# LTE_Module.net
KiCad netlist of a schematic drawn in Altium Designer
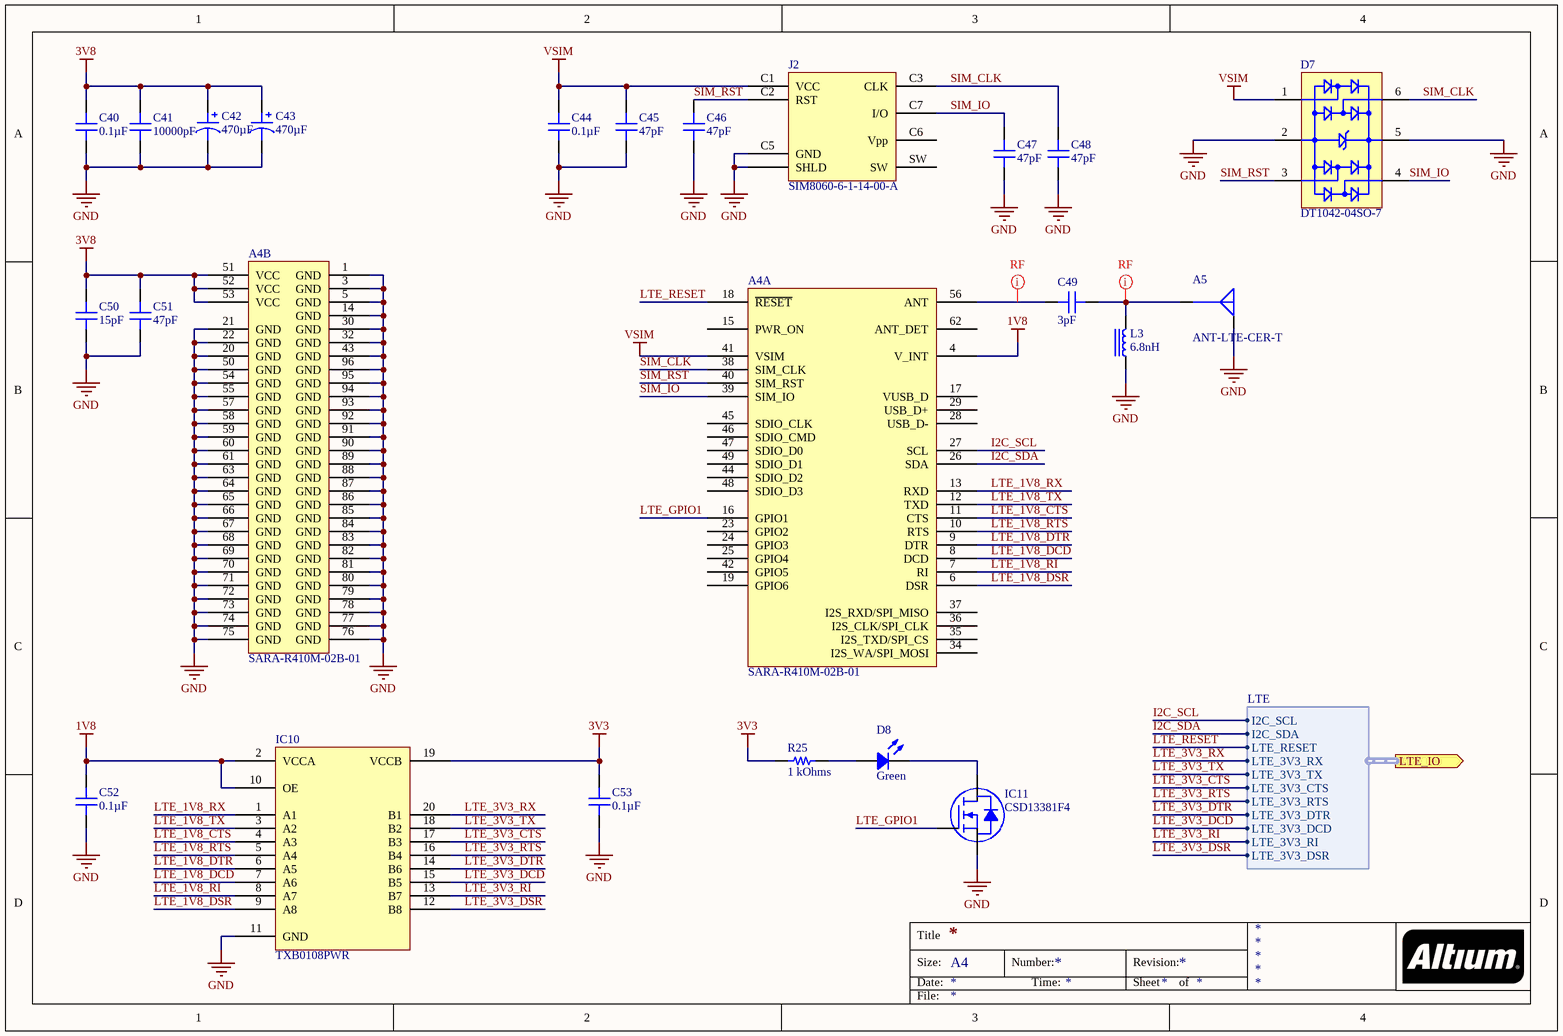
[diagram p0: LTE Module.SchDoc]

(export (version "E")
  (design (tool "Eeschema 10.0.6"))
  (components
    (comp (ref "A4")
      (value "SARA-R410M-02B-01")
      (footprint "U-BLOX SARA-R4")
      (description "RF TXRX CELL 4G LTE CATM1/NB-IOT")
      (fields (field (name "MANUFACTURER") "U-Blox America Inc."))
      (libsource (lib "Celestial Altium Library - altium_library") (part "U-BLOX SARA-R410M-02B-01"))
    )
    (comp (ref "A5")
      (value "ANT-LTE-CER-T")
      (footprint "LINX ANT-LTE-CER-T")
      (description "RF ANT 829MHZ/1.94GHZ CHIP SLD")
      (fields (field (name "MANUFACTURER") "Linx Technologies Inc."))
      (libsource (lib "Celestial Altium Library - altium_library") (part "Basic Antenna"))
    )
    (comp (ref "C40")
      (value "0.1µF")
      (footprint "CAP 0201_0603")
      (description "CAP CER 0.1UF 16V X5R 0201")
      (fields
        (field (name "PART NUMBER") "GRM033R61C104ME84D")
        (field (name "MANUFACTURER") "Murata Electronics")
      )
      (libsource (lib "Celestial Altium Library - altium_library") (part "Capacitor"))
    )
    (comp (ref "C41")
      (value "10000pF")
      (footprint "CAP 0201_0603")
      (description "CAP CER 10000PF 6.3V X7R 0201")
      (fields
        (field (name "PART NUMBER") "CGA1A2X7R0J103M030BA")
        (field (name "MANUFACTURER") "TDK Corporation")
      )
      (libsource (lib "Celestial Altium Library - altium_library") (part "Capacitor"))
    )
    (comp (ref "C42")
      (value "470µF")
      (footprint "CAP POL 1411_3528")
      (description "CAP TANT 470UF 20% 6.3V 1411")
      (fields (field (name "PART NUMBER") "F950J477MBAAQ2") (field (name "MANUFACTURER") "AVX Corporation"))
      (libsource (lib "Celestial Altium Library - altium_library") (part "Polarised Capacitor"))
    )
    (comp (ref "C43")
      (value "470µF")
      (footprint "CAP POL 1411_3528")
      (description "CAP TANT 470UF 20% 6.3V 1411")
      (fields (field (name "PART NUMBER") "F950J477MBAAQ2") (field (name "MANUFACTURER") "AVX Corporation"))
      (libsource (lib "Celestial Altium Library - altium_library") (part "Polarised Capacitor"))
    )
    (comp (ref "C44")
      (value "0.1µF")
      (footprint "CAP 0201_0603")
      (description "CAP CER 0.1UF 16V X5R 0201")
      (fields
        (field (name "PART NUMBER") "GRM033R61C104ME84D")
        (field (name "MANUFACTURER") "Murata Electronics")
      )
      (libsource (lib "Celestial Altium Library - altium_library") (part "Capacitor"))
    )
    (comp (ref "C45")
      (value "47pF")
      (footprint "CAP 0201_0603")
      (description "CAP CER 47PF 25V NP0 0201")
      (fields (field (name "PART NUMBER") "C0201C470K3GAC7867") (field (name "MANUFACTURER") "KEMET"))
      (libsource (lib "Celestial Altium Library - altium_library") (part "Capacitor"))
    )
    (comp (ref "C46")
      (value "47pF")
      (footprint "CAP 0201_0603")
      (description "CAP CER 47PF 25V NP0 0201")
      (fields (field (name "PART NUMBER") "C0201C470K3GAC7867") (field (name "MANUFACTURER") "KEMET"))
      (libsource (lib "Celestial Altium Library - altium_library") (part "Capacitor"))
    )
    (comp (ref "C47")
      (value "47pF")
      (footprint "CAP 0201_0603")
      (description "CAP CER 47PF 25V NP0 0201")
      (fields (field (name "PART NUMBER") "C0201C470K3GAC7867") (field (name "MANUFACTURER") "KEMET"))
      (libsource (lib "Celestial Altium Library - altium_library") (part "Capacitor"))
    )
    (comp (ref "C48")
      (value "47pF")
      (footprint "CAP 0201_0603")
      (description "CAP CER 47PF 25V NP0 0201")
      (fields (field (name "PART NUMBER") "C0201C470K3GAC7867") (field (name "MANUFACTURER") "KEMET"))
      (libsource (lib "Celestial Altium Library - altium_library") (part "Capacitor"))
    )
    (comp (ref "C49")
      (value "3pF")
      (footprint "CAP 0201_0603 RF")
      (description "CAP CER 3PF 25V C0G/NP0 0201")
      (fields
        (field (name "PART NUMBER") "GJM0335C1E3R0CB01D")
        (field (name "MANUFACTURER") "Murata Electronics")
      )
      (libsource (lib "Celestial Altium Library - altium_library") (part "Capacitor"))
    )
    (comp (ref "C50")
      (value "15pF")
      (footprint "CAP 0201_0603")
      (description "CAP CER 15PF 25V C0G 0201")
      (fields
        (field (name "PART NUMBER") "CGA1A2C0G1E150J030BA")
        (field (name "MANUFACTURER") "TDK Corporation")
      )
      (libsource (lib "Celestial Altium Library - altium_library") (part "Capacitor"))
    )
    (comp (ref "C51")
      (value "47pF")
      (footprint "CAP 0201_0603")
      (description "CAP CER 47PF 25V NP0 0201")
      (fields (field (name "PART NUMBER") "C0201C470K3GAC7867") (field (name "MANUFACTURER") "KEMET"))
      (libsource (lib "Celestial Altium Library - altium_library") (part "Capacitor"))
    )
    (comp (ref "C52")
      (value "0.1µF")
      (footprint "CAP 0201_0603")
      (description "CAP CER 0.1UF 16V X5R 0201")
      (fields
        (field (name "PART NUMBER") "GRM033R61C104ME84D")
        (field (name "MANUFACTURER") "Murata Electronics")
      )
      (libsource (lib "Celestial Altium Library - altium_library") (part "Capacitor"))
    )
    (comp (ref "C53")
      (value "0.1µF")
      (footprint "CAP 0201_0603")
      (description "CAP CER 0.1UF 16V X5R 0201")
      (fields
        (field (name "PART NUMBER") "GRM033R61C104ME84D")
        (field (name "MANUFACTURER") "Murata Electronics")
      )
      (libsource (lib "Celestial Altium Library - altium_library") (part "Capacitor"))
    )
    (comp (ref "D7")
      (value "DT1042-04SO-7")
      (footprint "DIODES SOT-23-6 W6")
      (description "TVS DIODE 5V 9V SOT26")
      (fields (field (name "MANUFACTURER") "Diodes Incorporated"))
      (libsource (lib "Celestial Altium Library - altium_library") (part "DIODES SOT-23-6"))
    )
    (comp (ref "D8")
      (value "Green")
      (footprint "LED 0402_1005 GREEN")
      (description "LED GREEN CLEAR 0402 SMD")
      (fields (field (name "PART NUMBER") "QBLP595-IG") (field (name "MANUFACTURER") "QT Brightek (QTB)"))
      (libsource (lib "Celestial Altium Library - altium_library") (part "LED"))
    )
    (comp (ref "IC10")
      (value "TXB0108PWR")
      (footprint "TI TSSOP-20 PW")
      (description "IC TRNSLTR BIDIRECTIONAL 20TSSOP")
      (fields (field (name "MANUFACTURER") "Texas Instruments"))
      (libsource (lib "Celestial Altium Library - altium_library") (part "TI TXB0108PWR"))
    )
    (comp (ref "IC11")
      (value "CSD13381F4")
      (footprint "TI 3-XFDFN F4 YJC")
      (description "MOSFET N-CH 12V 2.1A 3PICOSTAR")
      (fields (field (name "MANUFACTURER") "Texas Instruments"))
      (libsource (lib "Celestial Altium Library - altium_library") (part "TI CSD MOSFET N-CH F4"))
    )
    (comp (ref "J2")
      (value "SIM8060-6-1-14-00-A")
      (footprint "GCT SIM8060-6-1-14-00-A")
      (description "CONN SIM NANO HINGED 6P W/SWITCH")
      (fields (field (name "MANUFACTURER") "GCT"))
      (libsource (lib "Celestial Altium Library - altium_library") (part "GCT SIM8060-6-1-14-00-A"))
    )
    (comp (ref "L3")
      (value "6.8nH")
      (footprint "IND 0402_1005 RF WW")
      (description "FIXED IND 6.8NH 1.45A 68 MOHM")
      (fields
        (field (name "PART NUMBER") "LQW15AN6N8J8ZD")
        (field (name "MANUFACTURER") "Murata Electronics")
      )
      (libsource (lib "Celestial Altium Library - altium_library") (part "Inductor"))
    )
    (comp (ref "R25")
      (value "1 kOhms")
      (footprint "RES 0201_0603")
      (description "RES SMD 1K OHM 1% 1/20W 0201")
      (fields
        (field (name "PART NUMBER") "ERJ-1GNF1001C")
        (field (name "MANUFACTURER") "Panasonic Electronic Components")
      )
      (libsource (lib "Celestial Altium Library - altium_library") (part "Resistor"))
    )
  )
  (nets
    (net (code "2") (name "/I2C_SCL") (class "Default")
      (node (ref "A4") (pin "27") (pinfunction "SCL_27") (pintype "passive"))
    )
    (net (code "3") (name "/I2C_SDA") (class "Default")
      (node (ref "A4") (pin "26") (pinfunction "SDA_26") (pintype "passive"))
    )
    (net (code "4") (name "/LTE_1V8_CTS") (class "Default")
      (node (ref "A4") (pin "11") (pinfunction "CTS_11") (pintype "passive"))
      (node (ref "IC10") (pin "4") (pinfunction "A3_4") (pintype "passive"))
    )
    (net (code "5") (name "/LTE_1V8_DCD") (class "Default")
      (node (ref "A4") (pin "8") (pinfunction "DCD_8") (pintype "passive"))
      (node (ref "IC10") (pin "7") (pinfunction "A6_7") (pintype "passive"))
    )
    (net (code "6") (name "/LTE_1V8_DSR") (class "Default")
      (node (ref "A4") (pin "6") (pinfunction "DSR_6") (pintype "passive"))
      (node (ref "IC10") (pin "9") (pinfunction "A8_9") (pintype "passive"))
    )
    (net (code "7") (name "/LTE_1V8_DTR") (class "Default")
      (node (ref "A4") (pin "9") (pinfunction "DTR_9") (pintype "passive"))
      (node (ref "IC10") (pin "6") (pinfunction "A5_6") (pintype "passive"))
    )
    (net (code "8") (name "/LTE_1V8_RI") (class "Default")
      (node (ref "A4") (pin "7") (pinfunction "RI_7") (pintype "passive"))
      (node (ref "IC10") (pin "8") (pinfunction "A7_8") (pintype "passive"))
    )
    (net (code "9") (name "/LTE_1V8_RTS") (class "Default")
      (node (ref "A4") (pin "10") (pinfunction "RTS_10") (pintype "passive"))
      (node (ref "IC10") (pin "5") (pinfunction "A4_5") (pintype "passive"))
    )
    (net (code "10") (name "/LTE_1V8_RX") (class "Default")
      (node (ref "A4") (pin "13") (pinfunction "RXD_13") (pintype "passive"))
      (node (ref "IC10") (pin "1") (pinfunction "A1_1") (pintype "passive"))
    )
    (net (code "11") (name "/LTE_1V8_TX") (class "Default")
      (node (ref "A4") (pin "12") (pinfunction "TXD_12") (pintype "passive"))
      (node (ref "IC10") (pin "3") (pinfunction "A2_3") (pintype "passive"))
    )
    (net (code "12") (name "/LTE_3V3_CTS") (class "Default")
      (node (ref "IC10") (pin "17") (pinfunction "B3_17") (pintype "passive"))
    )
    (net (code "13") (name "/LTE_3V3_DCD") (class "Default")
      (node (ref "IC10") (pin "15") (pinfunction "B5_15") (pintype "passive"))
    )
    (net (code "14") (name "/LTE_3V3_DSR") (class "Default")
      (node (ref "IC10") (pin "12") (pinfunction "B8_12") (pintype "passive"))
    )
    (net (code "15") (name "/LTE_3V3_DTR") (class "Default")
      (node (ref "IC10") (pin "14") (pinfunction "B6_14") (pintype "passive"))
    )
    (net (code "16") (name "/LTE_3V3_RI") (class "Default")
      (node (ref "IC10") (pin "13") (pinfunction "B7_13") (pintype "passive"))
    )
    (net (code "17") (name "/LTE_3V3_RTS") (class "Default")
      (node (ref "IC10") (pin "16") (pinfunction "B4_16") (pintype "passive"))
    )
    (net (code "18") (name "/LTE_3V3_RX") (class "Default")
      (node (ref "IC10") (pin "20") (pinfunction "B1_20") (pintype "passive"))
    )
    (net (code "19") (name "/LTE_3V3_TX") (class "Default")
      (node (ref "IC10") (pin "18") (pinfunction "B2_18") (pintype "passive"))
    )
    (net (code "20") (name "/LTE_GPIO1") (class "Default")
      (node (ref "A4") (pin "16") (pinfunction "GPIO1_16") (pintype "passive"))
      (node (ref "IC11") (pin "G") (pinfunction "G_G") (pintype "passive"))
    )
    (net (code "21") (name "/LTE_RESET") (class "Default")
      (node (ref "A4") (pin "18") (pinfunction "~{RESET}_18") (pintype "passive"))
    )
    (net (code "22") (name "/SIM_CLK") (class "Default")
      (node (ref "A4") (pin "38") (pinfunction "SIM_CLK_38") (pintype "passive"))
      (node (ref "C48") (pin "2") (pinfunction "2_2") (pintype "passive"))
      (node (ref "D7") (pin "6") (pinfunction "I/O_4_6") (pintype "passive"))
      (node (ref "J2") (pin "C3") (pinfunction "CLK_C3") (pintype "passive"))
    )
    (net (code "23") (name "/SIM_IO") (class "Default")
      (node (ref "A4") (pin "39") (pinfunction "SIM_IO_39") (pintype "passive"))
      (node (ref "C47") (pin "2") (pinfunction "2_2") (pintype "passive"))
      (node (ref "D7") (pin "4") (pinfunction "I/O_3_4") (pintype "passive"))
      (node (ref "J2") (pin "C7") (pinfunction "I/O_C7") (pintype "passive"))
    )
    (net (code "24") (name "/SIM_RST") (class "Default")
      (node (ref "A4") (pin "40") (pinfunction "SIM_RST_40") (pintype "passive"))
      (node (ref "C46") (pin "2") (pinfunction "2_2") (pintype "passive"))
      (node (ref "D7") (pin "3") (pinfunction "I/O_2_3") (pintype "passive"))
      (node (ref "J2") (pin "C2") (pinfunction "RST_C2") (pintype "passive"))
    )
    (net (code "26") (name "1V8") (class "Default")
      (node (ref "A4") (pin "4") (pinfunction "V_INT_4") (pintype "passive"))
      (node (ref "C52") (pin "2") (pinfunction "2_2") (pintype "passive"))
      (node (ref "IC10") (pin "10") (pinfunction "OE_10") (pintype "passive"))
      (node (ref "IC10") (pin "2") (pinfunction "VCCA_2") (pintype "passive"))
    )
    (net (code "27") (name "3V3") (class "Default")
      (node (ref "C53") (pin "2") (pinfunction "2_2") (pintype "passive"))
      (node (ref "IC10") (pin "19") (pinfunction "VCCB_19") (pintype "passive"))
      (node (ref "R25") (pin "1") (pinfunction "1_1") (pintype "passive"))
    )
    (net (code "28") (name "3V8") (class "Default")
      (node (ref "A4") (pin "51") (pinfunction "VCC_51") (pintype "passive"))
      (node (ref "A4") (pin "52") (pinfunction "VCC_52") (pintype "passive"))
      (node (ref "A4") (pin "53") (pinfunction "VCC_53") (pintype "passive"))
      (node (ref "C40") (pin "2") (pinfunction "2_2") (pintype "passive"))
      (node (ref "C41") (pin "2") (pinfunction "2_2") (pintype "passive"))
      (node (ref "C42") (pin "1") (pinfunction "1_1") (pintype "passive"))
      (node (ref "C43") (pin "1") (pinfunction "1_1") (pintype "passive"))
      (node (ref "C50") (pin "2") (pinfunction "2_2") (pintype "passive"))
      (node (ref "C51") (pin "2") (pinfunction "2_2") (pintype "passive"))
    )
    (net (code "29") (name "GND") (class "Default")
      (node (ref "A4") (pin "1") (pinfunction "GND_1") (pintype "passive"))
      (node (ref "A4") (pin "14") (pinfunction "GND_14") (pintype "passive"))
      (node (ref "A4") (pin "20") (pinfunction "GND_20") (pintype "passive"))
      (node (ref "A4") (pin "21") (pinfunction "GND_21") (pintype "passive"))
      (node (ref "A4") (pin "22") (pinfunction "GND_22") (pintype "passive"))
      (node (ref "A4") (pin "3") (pinfunction "GND_3") (pintype "passive"))
      (node (ref "A4") (pin "30") (pinfunction "GND_30") (pintype "passive"))
      (node (ref "A4") (pin "32") (pinfunction "GND_32") (pintype "passive"))
      (node (ref "A4") (pin "43") (pinfunction "GND_43") (pintype "passive"))
      (node (ref "A4") (pin "5") (pinfunction "GND_5") (pintype "passive"))
      (node (ref "A4") (pin "50") (pinfunction "GND_50") (pintype "passive"))
      (node (ref "A4") (pin "54") (pinfunction "GND_54") (pintype "passive"))
      (node (ref "A4") (pin "55") (pinfunction "GND_55") (pintype "passive"))
      (node (ref "A4") (pin "57") (pinfunction "GND_57") (pintype "passive"))
      (node (ref "A4") (pin "58") (pinfunction "GND_58") (pintype "passive"))
      (node (ref "A4") (pin "59") (pinfunction "GND_59") (pintype "passive"))
      (node (ref "A4") (pin "60") (pinfunction "GND_60") (pintype "passive"))
      (node (ref "A4") (pin "61") (pinfunction "GND_61") (pintype "passive"))
      (node (ref "A4") (pin "63") (pinfunction "GND_63") (pintype "passive"))
      (node (ref "A4") (pin "64") (pinfunction "GND_64") (pintype "passive"))
      (node (ref "A4") (pin "65") (pinfunction "GND_65") (pintype "passive"))
      (node (ref "A4") (pin "66") (pinfunction "GND_66") (pintype "passive"))
      (node (ref "A4") (pin "67") (pinfunction "GND_67") (pintype "passive"))
      (node (ref "A4") (pin "68") (pinfunction "GND_68") (pintype "passive"))
      (node (ref "A4") (pin "69") (pinfunction "GND_69") (pintype "passive"))
      (node (ref "A4") (pin "70") (pinfunction "GND_70") (pintype "passive"))
      (node (ref "A4") (pin "71") (pinfunction "GND_71") (pintype "passive"))
      (node (ref "A4") (pin "72") (pinfunction "GND_72") (pintype "passive"))
      (node (ref "A4") (pin "73") (pinfunction "GND_73") (pintype "passive"))
      (node (ref "A4") (pin "74") (pinfunction "GND_74") (pintype "passive"))
      (node (ref "A4") (pin "75") (pinfunction "GND_75") (pintype "passive"))
      (node (ref "A4") (pin "76") (pinfunction "GND_76") (pintype "passive"))
      (node (ref "A4") (pin "77") (pinfunction "GND_77") (pintype "passive"))
      (node (ref "A4") (pin "78") (pinfunction "GND_78") (pintype "passive"))
      (node (ref "A4") (pin "79") (pinfunction "GND_79") (pintype "passive"))
      (node (ref "A4") (pin "80") (pinfunction "GND_80") (pintype "passive"))
      (node (ref "A4") (pin "81") (pinfunction "GND_81") (pintype "passive"))
      (node (ref "A4") (pin "82") (pinfunction "GND_82") (pintype "passive"))
      (node (ref "A4") (pin "83") (pinfunction "GND_83") (pintype "passive"))
      (node (ref "A4") (pin "84") (pinfunction "GND_84") (pintype "passive"))
      (node (ref "A4") (pin "85") (pinfunction "GND_85") (pintype "passive"))
      (node (ref "A4") (pin "86") (pinfunction "GND_86") (pintype "passive"))
      (node (ref "A4") (pin "87") (pinfunction "GND_87") (pintype "passive"))
      (node (ref "A4") (pin "88") (pinfunction "GND_88") (pintype "passive"))
      (node (ref "A4") (pin "89") (pinfunction "GND_89") (pintype "passive"))
      (node (ref "A4") (pin "90") (pinfunction "GND_90") (pintype "passive"))
      (node (ref "A4") (pin "91") (pinfunction "GND_91") (pintype "passive"))
      (node (ref "A4") (pin "92") (pinfunction "GND_92") (pintype "passive"))
      (node (ref "A4") (pin "93") (pinfunction "GND_93") (pintype "passive"))
      (node (ref "A4") (pin "94") (pinfunction "GND_94") (pintype "passive"))
      (node (ref "A4") (pin "95") (pinfunction "GND_95") (pintype "passive"))
      (node (ref "A4") (pin "96") (pinfunction "GND_96") (pintype "passive"))
      (node (ref "A5") (pin "G") (pinfunction "G_G") (pintype "passive"))
      (node (ref "C40") (pin "1") (pinfunction "1_1") (pintype "passive"))
      (node (ref "C41") (pin "1") (pinfunction "1_1") (pintype "passive"))
      (node (ref "C42") (pin "2") (pinfunction "2_2") (pintype "passive"))
      (node (ref "C43") (pin "2") (pinfunction "2_2") (pintype "passive"))
      (node (ref "C44") (pin "1") (pinfunction "1_1") (pintype "passive"))
      (node (ref "C45") (pin "1") (pinfunction "1_1") (pintype "passive"))
      (node (ref "C46") (pin "1") (pinfunction "1_1") (pintype "passive"))
      (node (ref "C47") (pin "1") (pinfunction "1_1") (pintype "passive"))
      (node (ref "C48") (pin "1") (pinfunction "1_1") (pintype "passive"))
      (node (ref "C50") (pin "1") (pinfunction "1_1") (pintype "passive"))
      (node (ref "C51") (pin "1") (pinfunction "1_1") (pintype "passive"))
      (node (ref "C52") (pin "1") (pinfunction "1_1") (pintype "passive"))
      (node (ref "C53") (pin "1") (pinfunction "1_1") (pintype "passive"))
      (node (ref "D7") (pin "2") (pinfunction "GND_2") (pintype "passive"))
      (node (ref "D7") (pin "5") (pinfunction "VBUS_5") (pintype "passive"))
      (node (ref "IC10") (pin "11") (pinfunction "GND_11") (pintype "passive"))
      (node (ref "IC11") (pin "S") (pinfunction "S_S") (pintype "passive"))
      (node (ref "J2") (pin "C5") (pinfunction "GND_C5") (pintype "passive"))
      (node (ref "J2") (pin "S") (pinfunction "SHLD_S") (pintype "passive"))
      (node (ref "L3") (pin "1") (pinfunction "1_1") (pintype "passive"))
    )
    (net (code "30") (name "Net-(A4A-ANT)") (class "Default")
      (node (ref "A4") (pin "56") (pinfunction "ANT_56") (pintype "passive"))
      (node (ref "C49") (pin "1") (pinfunction "1_1") (pintype "passive"))
    )
    (net (code "31") (name "Net-(A5-PadS)") (class "Default")
      (node (ref "A5") (pin "S") (pinfunction "S_S") (pintype "passive"))
      (node (ref "C49") (pin "2") (pinfunction "2_2") (pintype "passive"))
      (node (ref "L3") (pin "2") (pinfunction "2_2") (pintype "passive"))
    )
    (net (code "32") (name "Net-(D8-Pad1)") (class "Default")
      (node (ref "D8") (pin "1") (pinfunction "1_1") (pintype "passive"))
      (node (ref "R25") (pin "2") (pinfunction "2_2") (pintype "passive"))
    )
    (net (code "33") (name "Net-(D8-Pad2)") (class "Default")
      (node (ref "D8") (pin "2") (pinfunction "2_2") (pintype "passive"))
      (node (ref "IC11") (pin "D") (pinfunction "D_D") (pintype "passive"))
    )
    (net (code "34") (name "VSIM") (class "Default")
      (node (ref "A4") (pin "41") (pinfunction "VSIM_41") (pintype "passive"))
      (node (ref "C44") (pin "2") (pinfunction "2_2") (pintype "passive"))
      (node (ref "C45") (pin "2") (pinfunction "2_2") (pintype "passive"))
      (node (ref "D7") (pin "1") (pinfunction "I/O_1_1") (pintype "passive"))
      (node (ref "J2") (pin "C1") (pinfunction "VCC_C1") (pintype "passive"))
    )
    (net (code "35") (name "unconnected-(A4A-ANT_DET-Pad62)") (class "Default")
      (node (ref "A4") (pin "62") (pinfunction "ANT_DET_62") (pintype "passive"))
    )
    (net (code "36") (name "unconnected-(A4A-GPIO2-Pad23)") (class "Default")
      (node (ref "A4") (pin "23") (pinfunction "GPIO2_23") (pintype "passive"))
    )
    (net (code "37") (name "unconnected-(A4A-GPIO3-Pad24)") (class "Default")
      (node (ref "A4") (pin "24") (pinfunction "GPIO3_24") (pintype "passive"))
    )
    (net (code "38") (name "unconnected-(A4A-GPIO4-Pad25)") (class "Default")
      (node (ref "A4") (pin "25") (pinfunction "GPIO4_25") (pintype "passive"))
    )
    (net (code "39") (name "unconnected-(A4A-GPIO5-Pad42)") (class "Default")
      (node (ref "A4") (pin "42") (pinfunction "GPIO5_42") (pintype "passive"))
    )
    (net (code "40") (name "unconnected-(A4A-GPIO6-Pad19)") (class "Default")
      (node (ref "A4") (pin "19") (pinfunction "GPIO6_19") (pintype "passive"))
    )
    (net (code "41") (name "unconnected-(A4A-I2S_CLK{slash}SPI_CLK-Pad36)") (class "Default")
      (node (ref "A4") (pin "36") (pinfunction "I2S_CLK/SPI_CLK_36") (pintype "passive"))
    )
    (net (code "42") (name "unconnected-(A4A-I2S_RXD{slash}SPI_MISO-Pad37)") (class "Default")
      (node (ref "A4") (pin "37") (pinfunction "I2S_RXD/SPI_MISO_37") (pintype "passive"))
    )
    (net (code "43") (name "unconnected-(A4A-I2S_TXD{slash}SPI_CS-Pad35)") (class "Default")
      (node (ref "A4") (pin "35") (pinfunction "I2S_TXD/SPI_CS_35") (pintype "passive"))
    )
    (net (code "44") (name "unconnected-(A4A-I2S_WA{slash}SPI_MOSI-Pad34)") (class "Default")
      (node (ref "A4") (pin "34") (pinfunction "I2S_WA/SPI_MOSI_34") (pintype "passive"))
    )
    (net (code "45") (name "unconnected-(A4A-PWR_ON-Pad15)") (class "Default")
      (node (ref "A4") (pin "15") (pinfunction "PWR_ON_15") (pintype "passive"))
    )
    (net (code "46") (name "unconnected-(A4A-SDIO_CLK-Pad45)") (class "Default")
      (node (ref "A4") (pin "45") (pinfunction "SDIO_CLK_45") (pintype "passive"))
    )
    (net (code "47") (name "unconnected-(A4A-SDIO_CMD-Pad46)") (class "Default")
      (node (ref "A4") (pin "46") (pinfunction "SDIO_CMD_46") (pintype "passive"))
    )
    (net (code "48") (name "unconnected-(A4A-SDIO_D0-Pad47)") (class "Default")
      (node (ref "A4") (pin "47") (pinfunction "SDIO_D0_47") (pintype "passive"))
    )
    (net (code "49") (name "unconnected-(A4A-SDIO_D1-Pad49)") (class "Default")
      (node (ref "A4") (pin "49") (pinfunction "SDIO_D1_49") (pintype "passive"))
    )
    (net (code "50") (name "unconnected-(A4A-SDIO_D2-Pad44)") (class "Default")
      (node (ref "A4") (pin "44") (pinfunction "SDIO_D2_44") (pintype "passive"))
    )
    (net (code "51") (name "unconnected-(A4A-SDIO_D3-Pad48)") (class "Default")
      (node (ref "A4") (pin "48") (pinfunction "SDIO_D3_48") (pintype "passive"))
    )
    (net (code "52") (name "unconnected-(A4A-USB_D+-Pad29)") (class "Default")
      (node (ref "A4") (pin "29") (pinfunction "USB_D+_29") (pintype "passive"))
    )
    (net (code "53") (name "unconnected-(A4A-USB_D--Pad28)") (class "Default")
      (node (ref "A4") (pin "28") (pinfunction "USB_D-_28") (pintype "passive"))
    )
    (net (code "54") (name "unconnected-(A4A-VUSB_D-Pad17)") (class "Default")
      (node (ref "A4") (pin "17") (pinfunction "VUSB_D_17") (pintype "passive"))
    )
    (net (code "55") (name "unconnected-(J2-PadSW)") (class "Default")
      (node (ref "J2") (pin "SW") (pinfunction "SW_SW") (pintype "passive"))
    )
    (net (code "56") (name "unconnected-(J2-Vpp-PadC6)") (class "Default")
      (node (ref "J2") (pin "C6") (pinfunction "Vpp_C6") (pintype "passive"))
    )
  )
)
